# jusin_boad.net
KiCad netlist of a schematic drawn in EAGLE
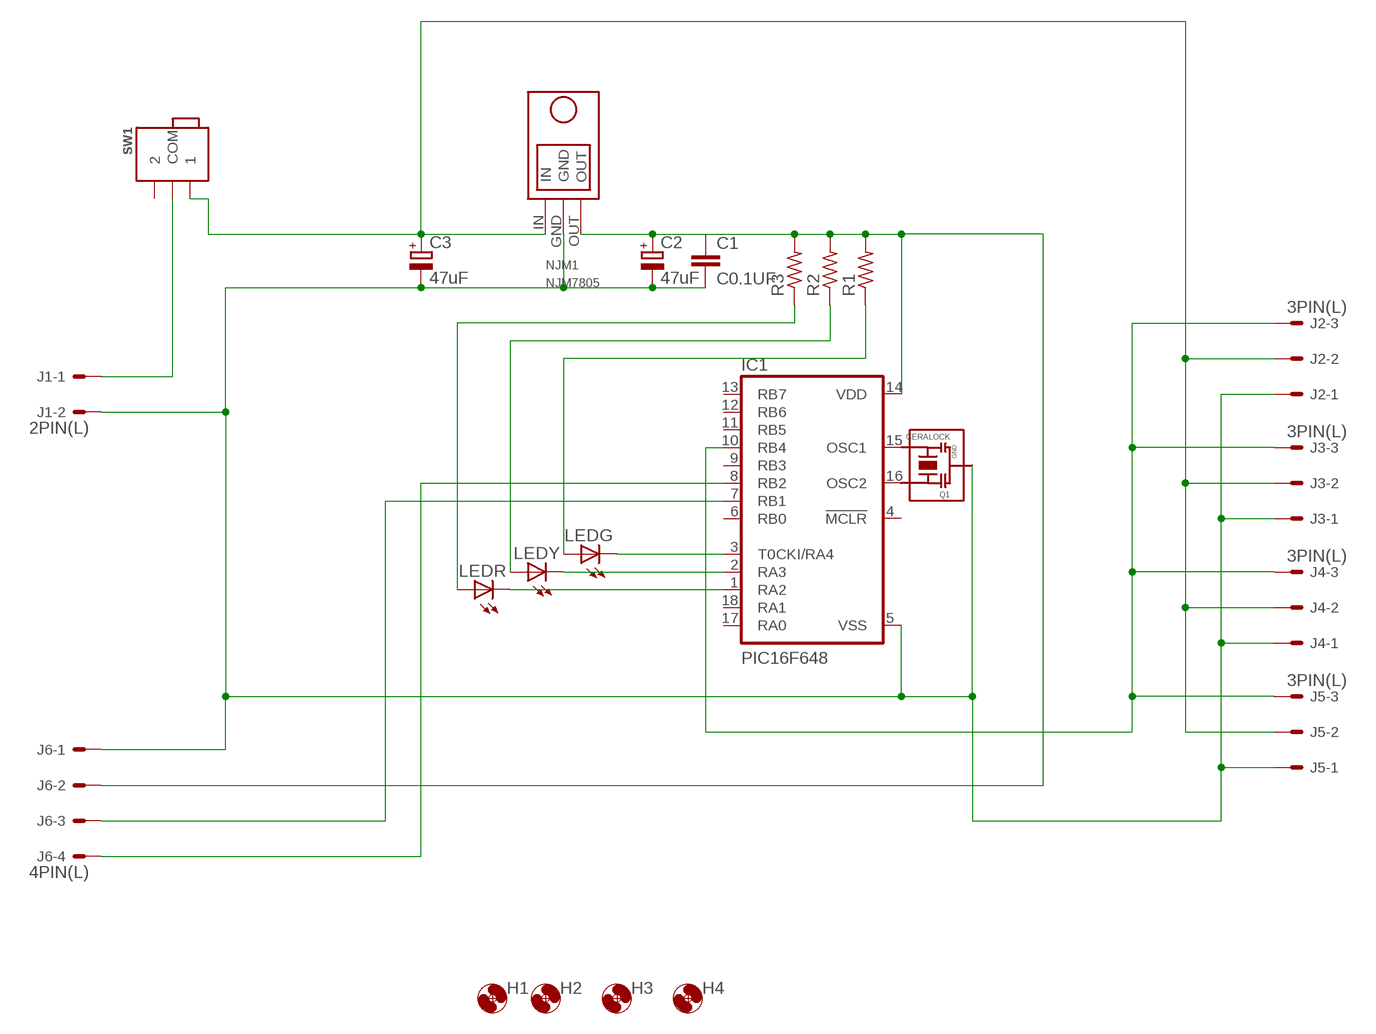
[diagram p0: schematic, sheet 1]

(export (version "E")
  (design (tool "Eeschema 10.0.6"))
  (components
    (comp (ref "C1")
      (value "C0.1UF")
      (footprint "eagle-import:C0.1UF")
      (libsource (lib "eagle-import") (part "C0.1UF"))
    )
    (comp (ref "C2")
      (value "47uF")
      (footprint "eagle-import:C-6MM")
      (libsource (lib "eagle-import") (part "C-ELEC"))
    )
    (comp (ref "C3")
      (value "47uF")
      (footprint "eagle-import:C-6MM")
      (libsource (lib "eagle-import") (part "C-ELEC"))
    )
    (comp (ref "H1")
      (value "HOLE3.3M3BOLT")
      (footprint "eagle-import:HOLE3.3")
      (libsource (lib "eagle-import") (part "HOLE3.3M3BOLT"))
    )
    (comp (ref "H2")
      (value "HOLE3.3M3BOLT")
      (footprint "eagle-import:HOLE3.3")
      (libsource (lib "eagle-import") (part "HOLE3.3M3BOLT"))
    )
    (comp (ref "H3")
      (value "HOLE3.3M3BOLT")
      (footprint "eagle-import:HOLE3.3")
      (libsource (lib "eagle-import") (part "HOLE3.3M3BOLT"))
    )
    (comp (ref "H4")
      (value "HOLE3.3M3BOLT")
      (footprint "eagle-import:HOLE3.3")
      (libsource (lib "eagle-import") (part "HOLE3.3M3BOLT"))
    )
    (comp (ref "IC1")
      (value "PIC16F648")
      (footprint "eagle-import:DIL18")
      (libsource (lib "eagle-import") (part "PIC16F648"))
    )
    (comp (ref "J1")
      (value "2PIN(L)")
      (footprint "eagle-import:2PL")
      (libsource (lib "eagle-import") (part "2PIN(L)"))
    )
    (comp (ref "J2")
      (value "3PIN(L)")
      (footprint "eagle-import:3PL")
      (libsource (lib "eagle-import") (part "3PIN(L)"))
    )
    (comp (ref "J3")
      (value "3PIN(L)")
      (footprint "eagle-import:3PL")
      (libsource (lib "eagle-import") (part "3PIN(L)"))
    )
    (comp (ref "J4")
      (value "3PIN(L)")
      (footprint "eagle-import:3PL")
      (libsource (lib "eagle-import") (part "3PIN(L)"))
    )
    (comp (ref "J5")
      (value "3PIN(L)")
      (footprint "eagle-import:3PL")
      (libsource (lib "eagle-import") (part "3PIN(L)"))
    )
    (comp (ref "J6")
      (value "4PIN(L)")
      (footprint "eagle-import:4PL")
      (libsource (lib "eagle-import") (part "4PIN(L)"))
    )
    (comp (ref "LEDG")
      (value "LED")
      (footprint "eagle-import:LED5MM")
      (libsource (lib "eagle-import") (part "LED"))
    )
    (comp (ref "LEDR")
      (value "LED")
      (footprint "eagle-import:LED5MM")
      (libsource (lib "eagle-import") (part "LED"))
    )
    (comp (ref "LEDY")
      (value "LED")
      (footprint "eagle-import:LED5MM")
      (libsource (lib "eagle-import") (part "LED"))
    )
    (comp (ref "NJM1")
      (value "NJM7805")
      (footprint "eagle-import:NJM7805")
      (libsource (lib "eagle-import") (part "NJM7805"))
    )
    (comp (ref "Q1")
      (value "CERALOCK")
      (footprint "eagle-import:CERALOCK")
      (libsource (lib "eagle-import") (part "CERALOCK"))
    )
    (comp (ref "R1")
      (value "R-")
      (footprint "eagle-import:0207_10")
      (libsource (lib "eagle-import") (part "R-"))
    )
    (comp (ref "R2")
      (value "R-")
      (footprint "eagle-import:0207_10")
      (libsource (lib "eagle-import") (part "R-"))
    )
    (comp (ref "R3")
      (value "R-")
      (footprint "eagle-import:0207_10")
      (libsource (lib "eagle-import") (part "R-"))
    )
    (comp (ref "SW1")
      (value "SWITCH_MININORMAL")
      (footprint "eagle-import:SWITCH_MINI")
      (libsource (lib "eagle-import") (part "SWITCH_MININORMAL"))
    )
  )
  (nets
    (net (code "1") (name "Net-(IC1-OSC1)") (class "Default")
      (node (ref "IC1") (pin "15") (pinfunction "OSC1_15") (pintype "input"))
      (node (ref "Q1") (pin "P$3") (pinfunction "P$3_P$3") (pintype "passive"))
    )
    (net (code "2") (name "Net-(IC1-OSC2)") (class "Default")
      (node (ref "IC1") (pin "16") (pinfunction "OSC2_16") (pintype "output"))
      (node (ref "Q1") (pin "P$1") (pinfunction "P$1_P$1") (pintype "passive"))
    )
    (net (code "3") (name "Net-(IC1-RA2)") (class "Default")
      (node (ref "IC1") (pin "1") (pinfunction "RA2_1") (pintype "bidirectional"))
      (node (ref "LEDR") (pin "K") (pinfunction "C_K") (pintype "passive"))
    )
    (net (code "4") (name "Net-(IC1-RA3)") (class "Default")
      (node (ref "IC1") (pin "2") (pinfunction "RA3_2") (pintype "bidirectional"))
      (node (ref "LEDY") (pin "K") (pinfunction "C_K") (pintype "passive"))
    )
    (net (code "5") (name "Net-(IC1-RB1)") (class "Default")
      (node (ref "IC1") (pin "7") (pinfunction "RB1_7") (pintype "bidirectional"))
      (node (ref "J6") (pin "3") (pinfunction "S_3") (pintype "passive"))
    )
    (net (code "6") (name "Net-(IC1-RB2)") (class "Default")
      (node (ref "IC1") (pin "8") (pinfunction "RB2_8") (pintype "bidirectional"))
      (node (ref "J6") (pin "4") (pinfunction "S_4") (pintype "passive"))
    )
    (net (code "7") (name "Net-(IC1-RB4)") (class "Default")
      (node (ref "IC1") (pin "10") (pinfunction "RB4_10") (pintype "bidirectional"))
      (node (ref "J2") (pin "3") (pinfunction "S_3") (pintype "passive"))
      (node (ref "J3") (pin "3") (pinfunction "S_3") (pintype "passive"))
      (node (ref "J4") (pin "3") (pinfunction "S_3") (pintype "passive"))
      (node (ref "J5") (pin "3") (pinfunction "S_3") (pintype "passive"))
    )
    (net (code "8") (name "Net-(IC1-T0CKI{slash}RA4)") (class "Default")
      (node (ref "IC1") (pin "3") (pinfunction "T0CKI/RA4_3") (pintype "bidirectional"))
      (node (ref "LEDG") (pin "K") (pinfunction "C_K") (pintype "passive"))
    )
    (net (code "9") (name "Net-(IC1-VDD)") (class "Default")
      (node (ref "C1") (pin "1") (pinfunction "1_1") (pintype "passive"))
      (node (ref "C2") (pin "+") (pinfunction "+_+") (pintype "passive"))
      (node (ref "IC1") (pin "14") (pinfunction "VDD_14") (pintype "power_in"))
      (node (ref "J6") (pin "2") (pinfunction "S_2") (pintype "passive"))
      (node (ref "NJM1") (pin "OUT") (pinfunction "OUT_OUT") (pintype "bidirectional"))
      (node (ref "R1") (pin "2") (pinfunction "2_2") (pintype "passive"))
      (node (ref "R2") (pin "2") (pinfunction "2_2") (pintype "passive"))
      (node (ref "R3") (pin "2") (pinfunction "2_2") (pintype "passive"))
    )
    (net (code "10") (name "Net-(IC1-VSS)") (class "Default")
      (node (ref "C1") (pin "2") (pinfunction "2_2") (pintype "passive"))
      (node (ref "C2") (pin "-") (pinfunction "-_-") (pintype "passive"))
      (node (ref "C3") (pin "-") (pinfunction "-_-") (pintype "passive"))
      (node (ref "IC1") (pin "5") (pinfunction "VSS_5") (pintype "power_in"))
      (node (ref "J1") (pin "2") (pinfunction "S_2") (pintype "passive"))
      (node (ref "J2") (pin "1") (pinfunction "S_1") (pintype "passive"))
      (node (ref "J3") (pin "1") (pinfunction "S_1") (pintype "passive"))
      (node (ref "J4") (pin "1") (pinfunction "S_1") (pintype "passive"))
      (node (ref "J5") (pin "1") (pinfunction "S_1") (pintype "passive"))
      (node (ref "J6") (pin "1") (pinfunction "S_1") (pintype "passive"))
      (node (ref "NJM1") (pin "GND") (pinfunction "GND_GND") (pintype "bidirectional"))
      (node (ref "Q1") (pin "P$2") (pinfunction "P$2_P$2") (pintype "passive"))
    )
    (net (code "11") (name "Net-(J1A-S)") (class "Default")
      (node (ref "J1") (pin "1") (pinfunction "S_1") (pintype "passive"))
      (node (ref "SW1") (pin "COM") (pinfunction "COM_COM") (pintype "passive"))
    )
    (net (code "12") (name "Net-(J2B-S)") (class "Default")
      (node (ref "C3") (pin "+") (pinfunction "+_+") (pintype "passive"))
      (node (ref "J2") (pin "2") (pinfunction "S_2") (pintype "passive"))
      (node (ref "J3") (pin "2") (pinfunction "S_2") (pintype "passive"))
      (node (ref "J4") (pin "2") (pinfunction "S_2") (pintype "passive"))
      (node (ref "J5") (pin "2") (pinfunction "S_2") (pintype "passive"))
      (node (ref "NJM1") (pin "IN") (pinfunction "IN_IN") (pintype "bidirectional"))
      (node (ref "SW1") (pin "1") (pinfunction "1_1") (pintype "passive"))
    )
    (net (code "13") (name "Net-(LEDG-PadA)") (class "Default")
      (node (ref "LEDG") (pin "A") (pinfunction "A_A") (pintype "passive"))
      (node (ref "R1") (pin "1") (pinfunction "1_1") (pintype "passive"))
    )
    (net (code "14") (name "Net-(LEDR-PadA)") (class "Default")
      (node (ref "LEDR") (pin "A") (pinfunction "A_A") (pintype "passive"))
      (node (ref "R3") (pin "1") (pinfunction "1_1") (pintype "passive"))
    )
    (net (code "15") (name "Net-(LEDY-PadA)") (class "Default")
      (node (ref "LEDY") (pin "A") (pinfunction "A_A") (pintype "passive"))
      (node (ref "R2") (pin "1") (pinfunction "1_1") (pintype "passive"))
    )
    (net (code "16") (name "unconnected-(IC1-RA0-Pad17)") (class "Default")
      (node (ref "IC1") (pin "17") (pinfunction "RA0_17") (pintype "bidirectional"))
    )
    (net (code "17") (name "unconnected-(IC1-RA1-Pad18)") (class "Default")
      (node (ref "IC1") (pin "18") (pinfunction "RA1_18") (pintype "bidirectional"))
    )
    (net (code "18") (name "unconnected-(IC1-RB0-Pad6)") (class "Default")
      (node (ref "IC1") (pin "6") (pinfunction "RB0_6") (pintype "bidirectional"))
    )
    (net (code "19") (name "unconnected-(IC1-RB3-Pad9)") (class "Default")
      (node (ref "IC1") (pin "9") (pinfunction "RB3_9") (pintype "bidirectional"))
    )
    (net (code "20") (name "unconnected-(IC1-RB5-Pad11)") (class "Default")
      (node (ref "IC1") (pin "11") (pinfunction "RB5_11") (pintype "bidirectional"))
    )
    (net (code "21") (name "unconnected-(IC1-RB6-Pad12)") (class "Default")
      (node (ref "IC1") (pin "12") (pinfunction "RB6_12") (pintype "bidirectional"))
    )
    (net (code "22") (name "unconnected-(IC1-RB7-Pad13)") (class "Default")
      (node (ref "IC1") (pin "13") (pinfunction "RB7_13") (pintype "bidirectional"))
    )
    (net (code "23") (name "unconnected-(IC1-~{MCLR}-Pad4)") (class "Default")
      (node (ref "IC1") (pin "4") (pinfunction "~{MCLR}_4") (pintype "input"))
    )
    (net (code "24") (name "unconnected-(SW1-Pad2)") (class "Default")
      (node (ref "SW1") (pin "2") (pinfunction "2_2") (pintype "no_connect"))
    )
  )
)
